# ai_aerial.net
KiCad netlist of a schematic drawn in EAGLE
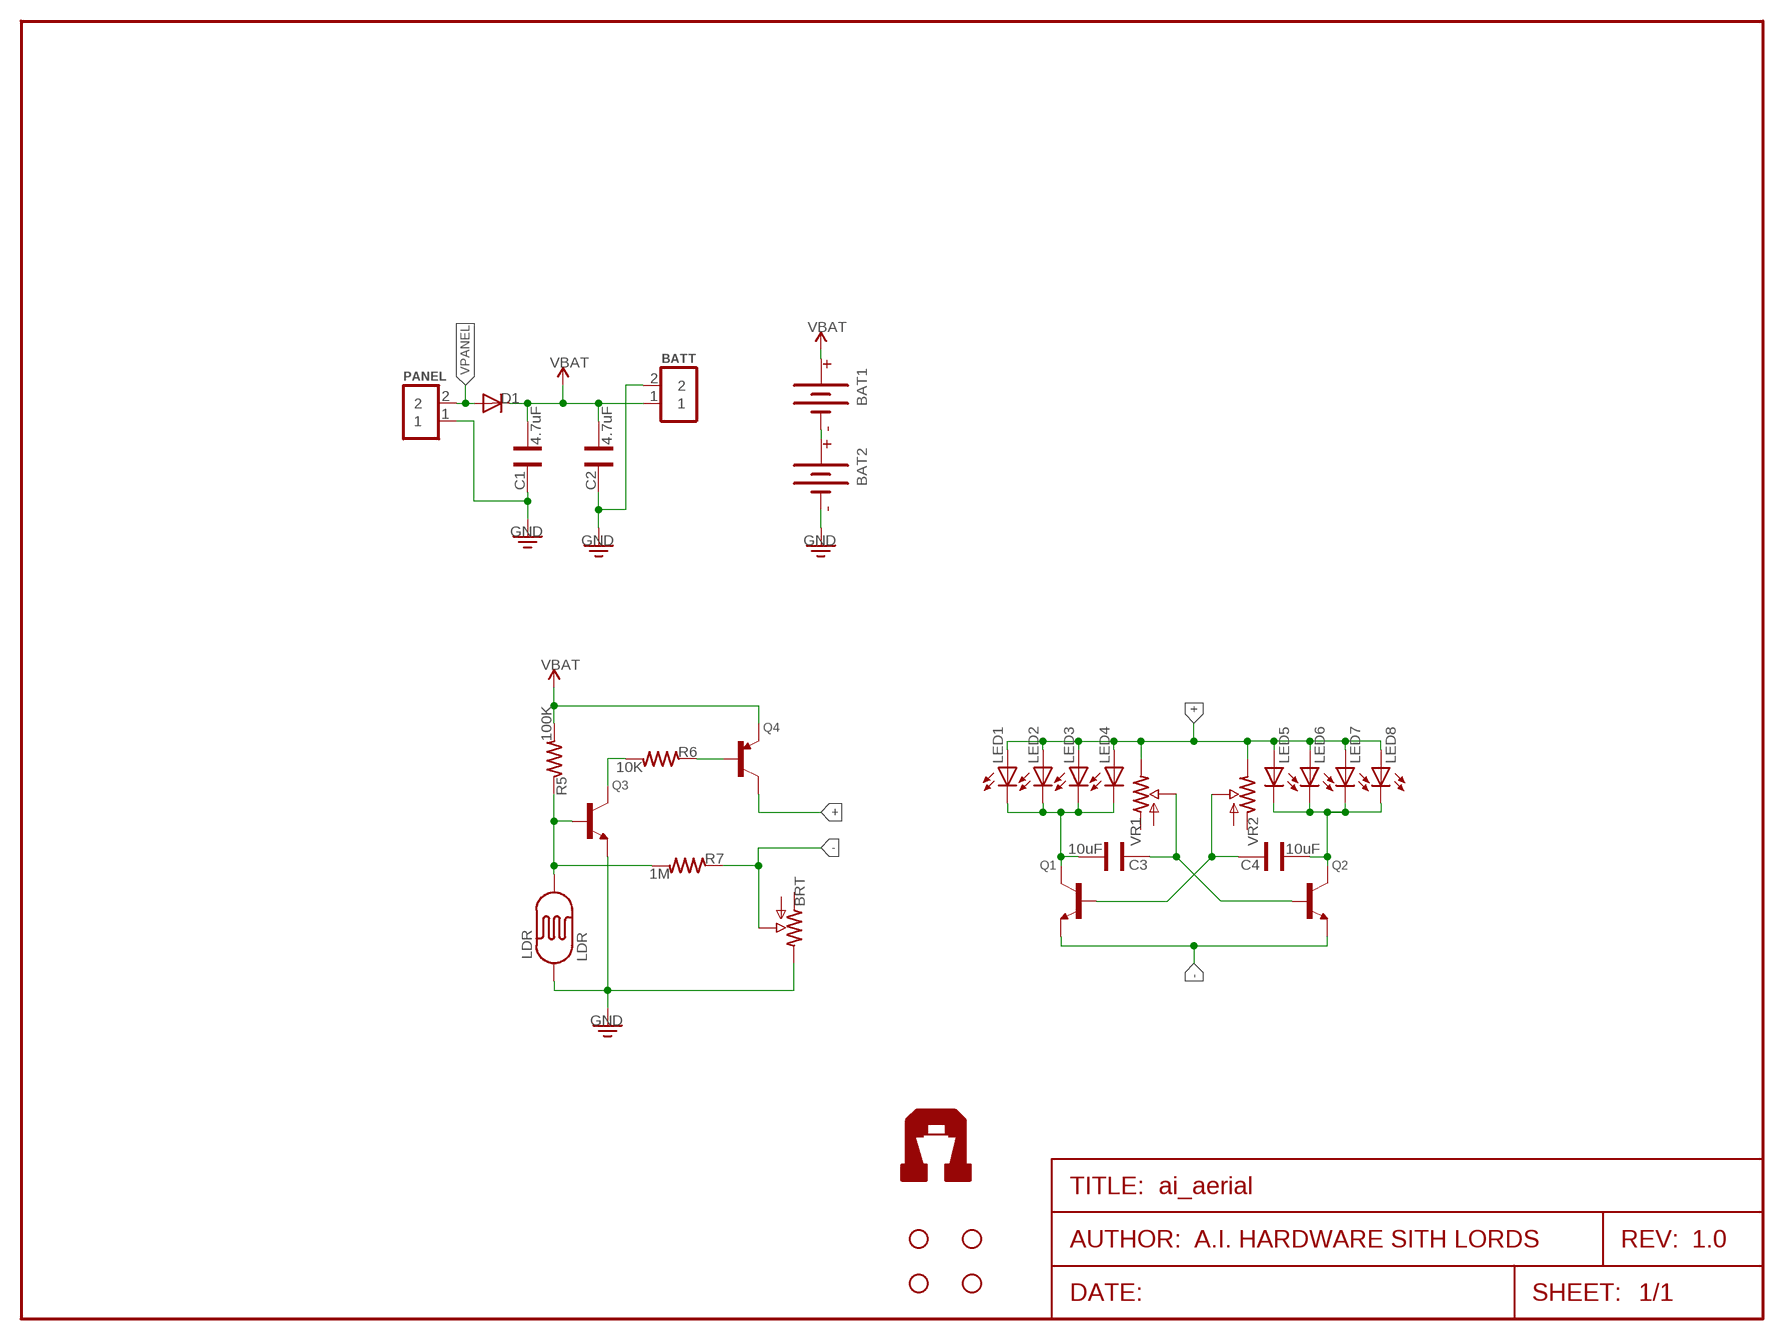
[diagram p0: schematic, sheet 1]

(export (version "E")
  (design (tool "Eeschema 10.0.6"))
  (components
    (comp (ref "BAT1")
      (value "BATTERY-HOLDER")
      (footprint "eagle-import:BATTERY-AAA")
      (libsource (lib "eagle-import") (part "BATTERY-HOLDER"))
    )
    (comp (ref "BAT2")
      (value "BATTERY-HOLDER")
      (footprint "eagle-import:BATTERY-AAA")
      (libsource (lib "eagle-import") (part "BATTERY-HOLDER"))
    )
    (comp (ref "BATT")
      (value "1X02ST")
      (footprint "eagle-import:1X02-ST")
      (libsource (lib "eagle-import") (part "1X02ST"))
    )
    (comp (ref "BRT")
      (value "POT05X05")
      (footprint "eagle-import:POT-05X05")
      (libsource (lib "eagle-import") (part "POT05X05"))
    )
    (comp (ref "C1")
      (value "4.7uF")
      (footprint "eagle-import:CAP-025X050")
      (libsource (lib "eagle-import") (part "CAP025X050"))
    )
    (comp (ref "C2")
      (value "4.7uF")
      (footprint "eagle-import:CAP-025X050")
      (libsource (lib "eagle-import") (part "CAP025X050"))
    )
    (comp (ref "C3")
      (value "10uF")
      (footprint "eagle-import:CAP-025X050")
      (libsource (lib "eagle-import") (part "CAP025X050"))
    )
    (comp (ref "C4")
      (value "10uF")
      (footprint "eagle-import:CAP-025X050")
      (libsource (lib "eagle-import") (part "CAP025X050"))
    )
    (comp (ref "D1")
      (value "DIODETH-1N914")
      (footprint "eagle-import:TH-1N914")
      (libsource (lib "eagle-import") (part "DIODETH-1N914"))
    )
    (comp (ref "LDR")
      (value "LDR-PTH")
      (footprint "eagle-import:LDR")
      (libsource (lib "eagle-import") (part "LDR-PTH"))
    )
    (comp (ref "LED1")
      (value "LED5MM")
      (footprint "eagle-import:LED-5MM")
      (libsource (lib "eagle-import") (part "LED5MM"))
    )
    (comp (ref "LED2")
      (value "LED5MM")
      (footprint "eagle-import:LED-5MM")
      (libsource (lib "eagle-import") (part "LED5MM"))
    )
    (comp (ref "LED3")
      (value "LED5MM")
      (footprint "eagle-import:LED-5MM")
      (libsource (lib "eagle-import") (part "LED5MM"))
    )
    (comp (ref "LED4")
      (value "LED5MM")
      (footprint "eagle-import:LED-5MM")
      (libsource (lib "eagle-import") (part "LED5MM"))
    )
    (comp (ref "LED5")
      (value "LED5MM")
      (footprint "eagle-import:LED-5MM")
      (libsource (lib "eagle-import") (part "LED5MM"))
    )
    (comp (ref "LED6")
      (value "LED5MM")
      (footprint "eagle-import:LED-5MM")
      (libsource (lib "eagle-import") (part "LED5MM"))
    )
    (comp (ref "LED7")
      (value "LED5MM")
      (footprint "eagle-import:LED-5MM")
      (libsource (lib "eagle-import") (part "LED5MM"))
    )
    (comp (ref "LED8")
      (value "LED5MM")
      (footprint "eagle-import:LED-5MM")
      (libsource (lib "eagle-import") (part "LED5MM"))
    )
    (comp (ref "PANEL")
      (value "1X02ST")
      (footprint "eagle-import:1X02-ST")
      (libsource (lib "eagle-import") (part "1X02ST"))
    )
    (comp (ref "Q1")
      (value "TRANSISTOR-NPN")
      (footprint "eagle-import:TO-92-NPN")
      (libsource (lib "eagle-import") (part "TRANSISTOR-NPN"))
    )
    (comp (ref "Q2")
      (value "TRANSISTOR-NPN")
      (footprint "eagle-import:TO-92-NPN")
      (libsource (lib "eagle-import") (part "TRANSISTOR-NPN"))
    )
    (comp (ref "Q3")
      (value "TRANSISTOR-NPN")
      (footprint "eagle-import:TO-92-NPN")
      (libsource (lib "eagle-import") (part "TRANSISTOR-NPN"))
    )
    (comp (ref "Q4")
      (value "TRANSISTOR-PNP")
      (footprint "eagle-import:TO-92-PNP")
      (libsource (lib "eagle-import") (part "TRANSISTOR-PNP"))
    )
    (comp (ref "R5")
      (value "100K")
      (footprint "eagle-import:RES-AXIAL-0.4")
      (libsource (lib "eagle-import") (part "RESAXIAL-0.4"))
    )
    (comp (ref "R6")
      (value "10K")
      (footprint "eagle-import:RES-AXIAL-0.4")
      (libsource (lib "eagle-import") (part "RESAXIAL-0.4"))
    )
    (comp (ref "R7")
      (value "1M")
      (footprint "eagle-import:RES-AXIAL-0.4")
      (libsource (lib "eagle-import") (part "RESAXIAL-0.4"))
    )
    (comp (ref "STANDOFF1")
      (value "STAND-OFF")
      (footprint "eagle-import:STAND-OFF")
      (libsource (lib "eagle-import") (part "STAND-OFF"))
    )
    (comp (ref "STANDOFF2")
      (value "STAND-OFF")
      (footprint "eagle-import:STAND-OFF")
      (libsource (lib "eagle-import") (part "STAND-OFF"))
    )
    (comp (ref "STANDOFF3")
      (value "STAND-OFF")
      (footprint "eagle-import:STAND-OFF")
      (libsource (lib "eagle-import") (part "STAND-OFF"))
    )
    (comp (ref "STANDOFF4")
      (value "STAND-OFF")
      (footprint "eagle-import:STAND-OFF")
      (libsource (lib "eagle-import") (part "STAND-OFF"))
    )
    (comp (ref "U$4")
      (value "AI-LOGOM")
      (footprint "eagle-import:AI-LOGO-M")
      (libsource (lib "eagle-import") (part "AI-LOGOM"))
    )
    (comp (ref "VR1")
      (value "POT05X05")
      (footprint "eagle-import:POT-05X05")
      (libsource (lib "eagle-import") (part "POT05X05"))
    )
    (comp (ref "VR2")
      (value "POT05X05")
      (footprint "eagle-import:POT-05X05")
      (libsource (lib "eagle-import") (part "POT05X05"))
    )
  )
  (nets
    (net (code "1") (name "+") (class "Default")
      (node (ref "LED1") (pin "A") (pinfunction "A_A") (pintype "passive"))
      (node (ref "LED2") (pin "A") (pinfunction "A_A") (pintype "passive"))
      (node (ref "LED3") (pin "A") (pinfunction "A_A") (pintype "passive"))
      (node (ref "LED4") (pin "A") (pinfunction "A_A") (pintype "passive"))
      (node (ref "LED5") (pin "A") (pinfunction "A_A") (pintype "passive"))
      (node (ref "LED6") (pin "A") (pinfunction "A_A") (pintype "passive"))
      (node (ref "LED7") (pin "A") (pinfunction "A_A") (pintype "passive"))
      (node (ref "LED8") (pin "A") (pinfunction "A_A") (pintype "passive"))
      (node (ref "Q4") (pin "1") (pinfunction "C_1") (pintype "passive"))
      (node (ref "VR1") (pin "1") (pinfunction "E_1") (pintype "passive"))
      (node (ref "VR2") (pin "1") (pinfunction "E_1") (pintype "passive"))
    )
    (net (code "2") (name "-") (class "Default")
      (node (ref "BRT") (pin "2") (pinfunction "S_2") (pintype "passive"))
      (node (ref "Q1") (pin "1") (pinfunction "E_1") (pintype "passive"))
      (node (ref "Q2") (pin "1") (pinfunction "E_1") (pintype "passive"))
      (node (ref "R7") (pin "P$1") (pinfunction "1_P$1") (pintype "passive"))
    )
    (net (code "3") (name "GND") (class "Default")
      (node (ref "BAT2") (pin "GND@1") (pinfunction "-_GND@1") (pintype "power_in"))
      (node (ref "BAT2") (pin "GND@2") (pinfunction "-_GND@2") (pintype "power_in"))
      (node (ref "BATT") (pin "2") (pinfunction "2_2") (pintype "bidirectional"))
      (node (ref "BRT") (pin "1") (pinfunction "E_1") (pintype "passive"))
      (node (ref "C1") (pin "2") (pinfunction "2_2") (pintype "passive"))
      (node (ref "C2") (pin "2") (pinfunction "2_2") (pintype "passive"))
      (node (ref "LDR") (pin "1") (pinfunction "P$1_1") (pintype "bidirectional"))
      (node (ref "PANEL") (pin "1") (pinfunction "1_1") (pintype "bidirectional"))
      (node (ref "Q3") (pin "1") (pinfunction "E_1") (pintype "passive"))
    )
    (net (code "4") (name "Net-(BAT1---PadGND@1)") (class "Default")
      (node (ref "BAT1") (pin "GND@1") (pinfunction "-_GND@1") (pintype "power_in"))
      (node (ref "BAT1") (pin "GND@2") (pinfunction "-_GND@2") (pintype "power_in"))
      (node (ref "BAT2") (pin "PWR@1") (pinfunction "+_PWR@1") (pintype "power_in"))
      (node (ref "BAT2") (pin "PWR@2") (pinfunction "+_PWR@2") (pintype "power_in"))
    )
    (net (code "5") (name "Net-(LDR-P$2)") (class "Default")
      (node (ref "LDR") (pin "2") (pinfunction "P$2_2") (pintype "bidirectional"))
      (node (ref "Q3") (pin "2") (pinfunction "B_2") (pintype "passive"))
      (node (ref "R5") (pin "P$1") (pinfunction "1_P$1") (pintype "passive"))
      (node (ref "R7") (pin "P$2") (pinfunction "2_P$2") (pintype "passive"))
    )
    (net (code "6") (name "Net-(Q1-B)") (class "Default")
      (node (ref "C4") (pin "2") (pinfunction "2_2") (pintype "passive"))
      (node (ref "Q1") (pin "2") (pinfunction "B_2") (pintype "passive"))
      (node (ref "VR2") (pin "2") (pinfunction "S_2") (pintype "passive"))
    )
    (net (code "7") (name "Net-(Q1-C)") (class "Default")
      (node (ref "C3") (pin "1") (pinfunction "1_1") (pintype "passive"))
      (node (ref "LED1") (pin "C") (pinfunction "C_C") (pintype "passive"))
      (node (ref "LED2") (pin "C") (pinfunction "C_C") (pintype "passive"))
      (node (ref "LED3") (pin "C") (pinfunction "C_C") (pintype "passive"))
      (node (ref "LED4") (pin "C") (pinfunction "C_C") (pintype "passive"))
      (node (ref "Q1") (pin "3") (pinfunction "C_3") (pintype "passive"))
    )
    (net (code "8") (name "Net-(Q2-B)") (class "Default")
      (node (ref "C3") (pin "2") (pinfunction "2_2") (pintype "passive"))
      (node (ref "Q2") (pin "2") (pinfunction "B_2") (pintype "passive"))
      (node (ref "VR1") (pin "2") (pinfunction "S_2") (pintype "passive"))
    )
    (net (code "9") (name "Net-(Q2-C)") (class "Default")
      (node (ref "C4") (pin "1") (pinfunction "1_1") (pintype "passive"))
      (node (ref "LED5") (pin "C") (pinfunction "C_C") (pintype "passive"))
      (node (ref "LED6") (pin "C") (pinfunction "C_C") (pintype "passive"))
      (node (ref "LED7") (pin "C") (pinfunction "C_C") (pintype "passive"))
      (node (ref "LED8") (pin "C") (pinfunction "C_C") (pintype "passive"))
      (node (ref "Q2") (pin "3") (pinfunction "C_3") (pintype "passive"))
    )
    (net (code "10") (name "Net-(Q3-C)") (class "Default")
      (node (ref "Q3") (pin "3") (pinfunction "C_3") (pintype "passive"))
      (node (ref "R6") (pin "P$2") (pinfunction "2_P$2") (pintype "passive"))
    )
    (net (code "11") (name "Net-(Q4-B)") (class "Default")
      (node (ref "Q4") (pin "2") (pinfunction "B_2") (pintype "passive"))
      (node (ref "R6") (pin "P$1") (pinfunction "1_P$1") (pintype "passive"))
    )
    (net (code "12") (name "VBAT") (class "Default")
      (node (ref "BAT1") (pin "PWR@1") (pinfunction "+_PWR@1") (pintype "power_in"))
      (node (ref "BAT1") (pin "PWR@2") (pinfunction "+_PWR@2") (pintype "power_in"))
      (node (ref "BATT") (pin "1") (pinfunction "1_1") (pintype "bidirectional"))
      (node (ref "C1") (pin "1") (pinfunction "1_1") (pintype "passive"))
      (node (ref "C2") (pin "1") (pinfunction "1_1") (pintype "passive"))
      (node (ref "D1") (pin "C") (pinfunction "C_C") (pintype "passive"))
      (node (ref "Q4") (pin "3") (pinfunction "E_3") (pintype "passive"))
      (node (ref "R5") (pin "P$2") (pinfunction "2_P$2") (pintype "passive"))
    )
    (net (code "13") (name "VPANEL") (class "Default")
      (node (ref "D1") (pin "A") (pinfunction "A_A") (pintype "passive"))
      (node (ref "PANEL") (pin "2") (pinfunction "2_2") (pintype "bidirectional"))
    )
    (net (code "14") (name "unconnected-(BRT-A-Pad3)") (class "Default")
      (node (ref "BRT") (pin "3") (pinfunction "A_3") (pintype "passive"))
    )
    (net (code "15") (name "unconnected-(VR1-A-Pad3)") (class "Default")
      (node (ref "VR1") (pin "3") (pinfunction "A_3") (pintype "passive"))
    )
    (net (code "16") (name "unconnected-(VR2-A-Pad3)") (class "Default")
      (node (ref "VR2") (pin "3") (pinfunction "A_3") (pintype "passive"))
    )
  )
)
